# RS485-Test.net
KiCad netlist of a schematic drawn in Altium Designer
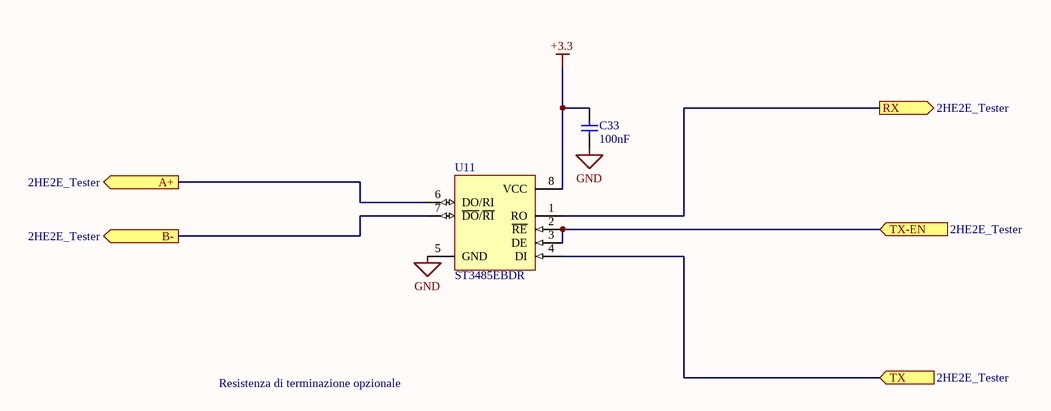
[diagram p0: RS485-Test.SchDoc]

(export (version "E")
  (design (tool "Eeschema 10.0.6"))
  (components
    (comp (ref "C33")
      (value "100nF")
      (footprint "0603M-C")
      (description "Ceramic Capacitor 25V")
      (fields (field (name "Comment") "Cap Ceramic"))
      (libsource (lib "Plume") (part "Cap Ceramic"))
    )
    (comp (ref "U11")
      (value "ST3485EBDR")
      (footprint "SOIC127P600-8N")
      (description "Multipoint RS-485/RS-422 Transceiver")
      (libsource (lib "Plume") (part "DS75176BM"))
    )
  )
  (nets
    (net (code "1") (name "+3.3") (class "Default")
      (node (ref "C33") (pin "1") (pinfunction "1_1") (pintype "passive"))
      (node (ref "U11") (pin "8") (pinfunction "VCC_8") (pintype "power_in"))
    )
    (net (code "2") (name "/A+") (class "Default")
      (node (ref "U11") (pin "6") (pinfunction "DO/RI_6") (pintype "bidirectional"))
    )
    (net (code "3") (name "/B-") (class "Default")
      (node (ref "U11") (pin "7") (pinfunction "~{DO}/~{RI}_7") (pintype "bidirectional"))
    )
    (net (code "4") (name "/RX") (class "Default")
      (node (ref "U11") (pin "1") (pinfunction "RO_1") (pintype "tri_state"))
    )
    (net (code "5") (name "/TX") (class "Default")
      (node (ref "U11") (pin "4") (pinfunction "DI_4") (pintype "input"))
    )
    (net (code "6") (name "/TX-EN") (class "Default")
      (node (ref "U11") (pin "2") (pinfunction "~{RE}_2") (pintype "input"))
      (node (ref "U11") (pin "3") (pinfunction "DE_3") (pintype "input"))
    )
    (net (code "7") (name "GND") (class "Default")
      (node (ref "C33") (pin "2") (pinfunction "2_2") (pintype "passive"))
      (node (ref "U11") (pin "5") (pinfunction "GND_5") (pintype "passive"))
    )
  )
)
